# 01_Filtr2.net
KiCad netlist of a schematic drawn in Altium Designer
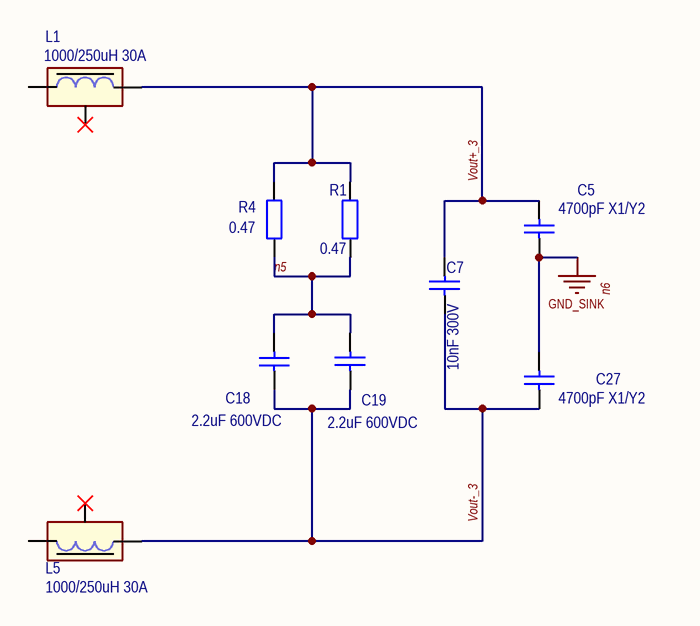
[diagram p0: 01_Filtr2.SchDoc]

(export (version "E")
  (design (tool "Eeschema 10.0.6"))
  (components
    (comp (ref "C5")
      (value "4700pF X1/Y2")
      (footprint "mainLib:SMD_C_2220")
      (description "SMD C2220 MURATA 250Vac 10% X7R X1Y2")
      (fields (field (name "PARTNUMBER") "DE2E3KY472MA3") (field (name "MANUFACTURER") "MURATA"))
      (libsource (lib "mainRCLib") (part "C X1Y2 4700pF SMD 2220 250Vac 10%"))
    )
    (comp (ref "C7")
      (value "10nF 300V")
      (footprint "mainLib:C Y2 D13 7.5b")
      (description "Ceramic D=14 LS=7.5 300VAC X1Y2")
      (fields (field (name "PARTNUMBER") "DE2F3KY103MA3") (field (name "MANUFACTURER") "Murata"))
      (libsource (lib "mainRCLib") (part "C X1Y2 10nF D13 LS7.5"))
    )
    (comp (ref "C18")
      (value "2.2uF 600VDC")
      (footprint "mainLib:MKP_W20_H39.5_L41.5_LS37.5")
      (description "Polypropelene W20 H39.5 L41.5 LS37.5 600VDC 10%")
      (fields (field (name "PARTNUMBER") "MKP1J042207G00K") (field (name "MANUFACTURER") "Wima"))
      (libsource (lib "mainRCLib") (part "MKP1 2.2uF 10% 600VDC"))
    )
    (comp (ref "C19")
      (value "2.2uF 600VDC")
      (footprint "mainLib:MKP_W20_H39.5_L41.5_LS37.5")
      (description "Polypropelene W20 H39.5 L41.5 LS37.5 600VDC 10%")
      (fields (field (name "PARTNUMBER") "MKP1J042207G00K") (field (name "MANUFACTURER") "Wima"))
      (libsource (lib "mainRCLib") (part "MKP1 2.2uF 10% 600VDC"))
    )
    (comp (ref "C27")
      (value "4700pF X1/Y2")
      (footprint "mainLib:SMD_C_2220")
      (description "SMD C2220 MURATA 250Vac 10% X7R X1Y2")
      (fields (field (name "PARTNUMBER") "DE2E3KY472MA3") (field (name "MANUFACTURER") "MURATA"))
      (libsource (lib "mainRCLib") (part "C X1Y2 4700pF SMD 2220 250Vac 10%"))
    )
    (comp (ref "L1")
      (value "1000/250uH 30A")
      (footprint "mainLib:Dross (1000/250 uH 30 A)AMAK.671111.033")
      (description "1000/250uH 30A  (Core T250-52 X2)")
      (fields (field (name "MANUFACTURER") "OLTEST") (field (name "PARTNUMBER") "R100.20.58.11.00"))
      (libsource (lib "") (part "Dross 1000/250uH 30A R100.20.58.11.00_1"))
    )
    (comp (ref "L5")
      (value "1000/250uH 30A")
      (footprint "mainLib:Dross (1000/250 uH 30 A)AMAK.671111.033")
      (description "1000/250uH 30A  (Core T250-52 X2)")
      (fields (field (name "MANUFACTURER") "OLTEST") (field (name "PARTNUMBER") "R100.20.58.11.00"))
      (libsource (lib "mainLib") (part "Dross 1000/250uH 30A R100.20.58.11.00"))
    )
    (comp (ref "R1")
      (value "0.47")
      (footprint "mainLib:PRW 10W 2050")
      (description "Выводной PRW 10W 0R47 +-5%")
      (fields (field (name "PARTNUMBER") "PRW0AWJW47K") (field (name "MANUFACTURER") "RoyalOhm"))
      (libsource (lib "mainRCLib") (part "PRW 0.47 10W +-5%"))
    )
    (comp (ref "R4")
      (value "0.47")
      (footprint "mainLib:PRW 10W 2050")
      (description "Выводной PRW 10W 0R47 +-5%")
      (fields (field (name "PARTNUMBER") "PRW0AWJW47K") (field (name "MANUFACTURER") "RoyalOhm"))
      (libsource (lib "mainRCLib") (part "PRW 0.47 10W +-5%"))
    )
  )
  (nets
    (net (code "1") (name "/Vout+_3") (class "Default")
      (node (ref "C5") (pin "2") (pinfunction "2_2") (pintype "passive"))
      (node (ref "C7") (pin "2") (pinfunction "2_2") (pintype "passive"))
      (node (ref "L1") (pin "2") (pinfunction "2_2") (pintype "passive"))
      (node (ref "R1") (pin "2") (pinfunction "2_2") (pintype "passive"))
      (node (ref "R4") (pin "2") (pinfunction "2_2") (pintype "passive"))
    )
    (net (code "2") (name "/Vout-_3") (class "Default")
      (node (ref "C18") (pin "2") (pinfunction "2_2") (pintype "passive"))
      (node (ref "C19") (pin "1") (pinfunction "1_1") (pintype "passive"))
      (node (ref "C27") (pin "1") (pinfunction "1_1") (pintype "passive"))
      (node (ref "C7") (pin "1") (pinfunction "1_1") (pintype "passive"))
      (node (ref "L5") (pin "1") (pinfunction "1_1") (pintype "passive"))
    )
    (net (code "3") (name "/n5") (class "Default")
      (node (ref "C18") (pin "1") (pinfunction "1_1") (pintype "passive"))
      (node (ref "C19") (pin "2") (pinfunction "2_2") (pintype "passive"))
      (node (ref "R1") (pin "1") (pinfunction "1_1") (pintype "passive"))
      (node (ref "R4") (pin "1") (pinfunction "1_1") (pintype "passive"))
    )
    (net (code "5") (name "GND_SINK") (class "Default")
      (node (ref "C27") (pin "2") (pinfunction "2_2") (pintype "passive"))
      (node (ref "C5") (pin "1") (pinfunction "1_1") (pintype "passive"))
    )
    (net (code "6") (name "unconnected-(L1-Pad1)") (class "Default")
      (node (ref "L1") (pin "1") (pinfunction "1_1") (pintype "passive"))
    )
    (net (code "7") (name "unconnected-(L1-Pad3)") (class "Default")
      (node (ref "L1") (pin "3") (pinfunction "3_3") (pintype "passive+no_connect"))
    )
    (net (code "8") (name "unconnected-(L5-Pad2)") (class "Default")
      (node (ref "L5") (pin "2") (pinfunction "2_2") (pintype "passive"))
    )
    (net (code "9") (name "unconnected-(L5-Pad3)") (class "Default")
      (node (ref "L5") (pin "3") (pinfunction "3_3") (pintype "passive+no_connect"))
    )
  )
)
